# Adafruit_TCS3448_14-Channel_Light_Color_.net
KiCad netlist of a schematic drawn in EAGLE
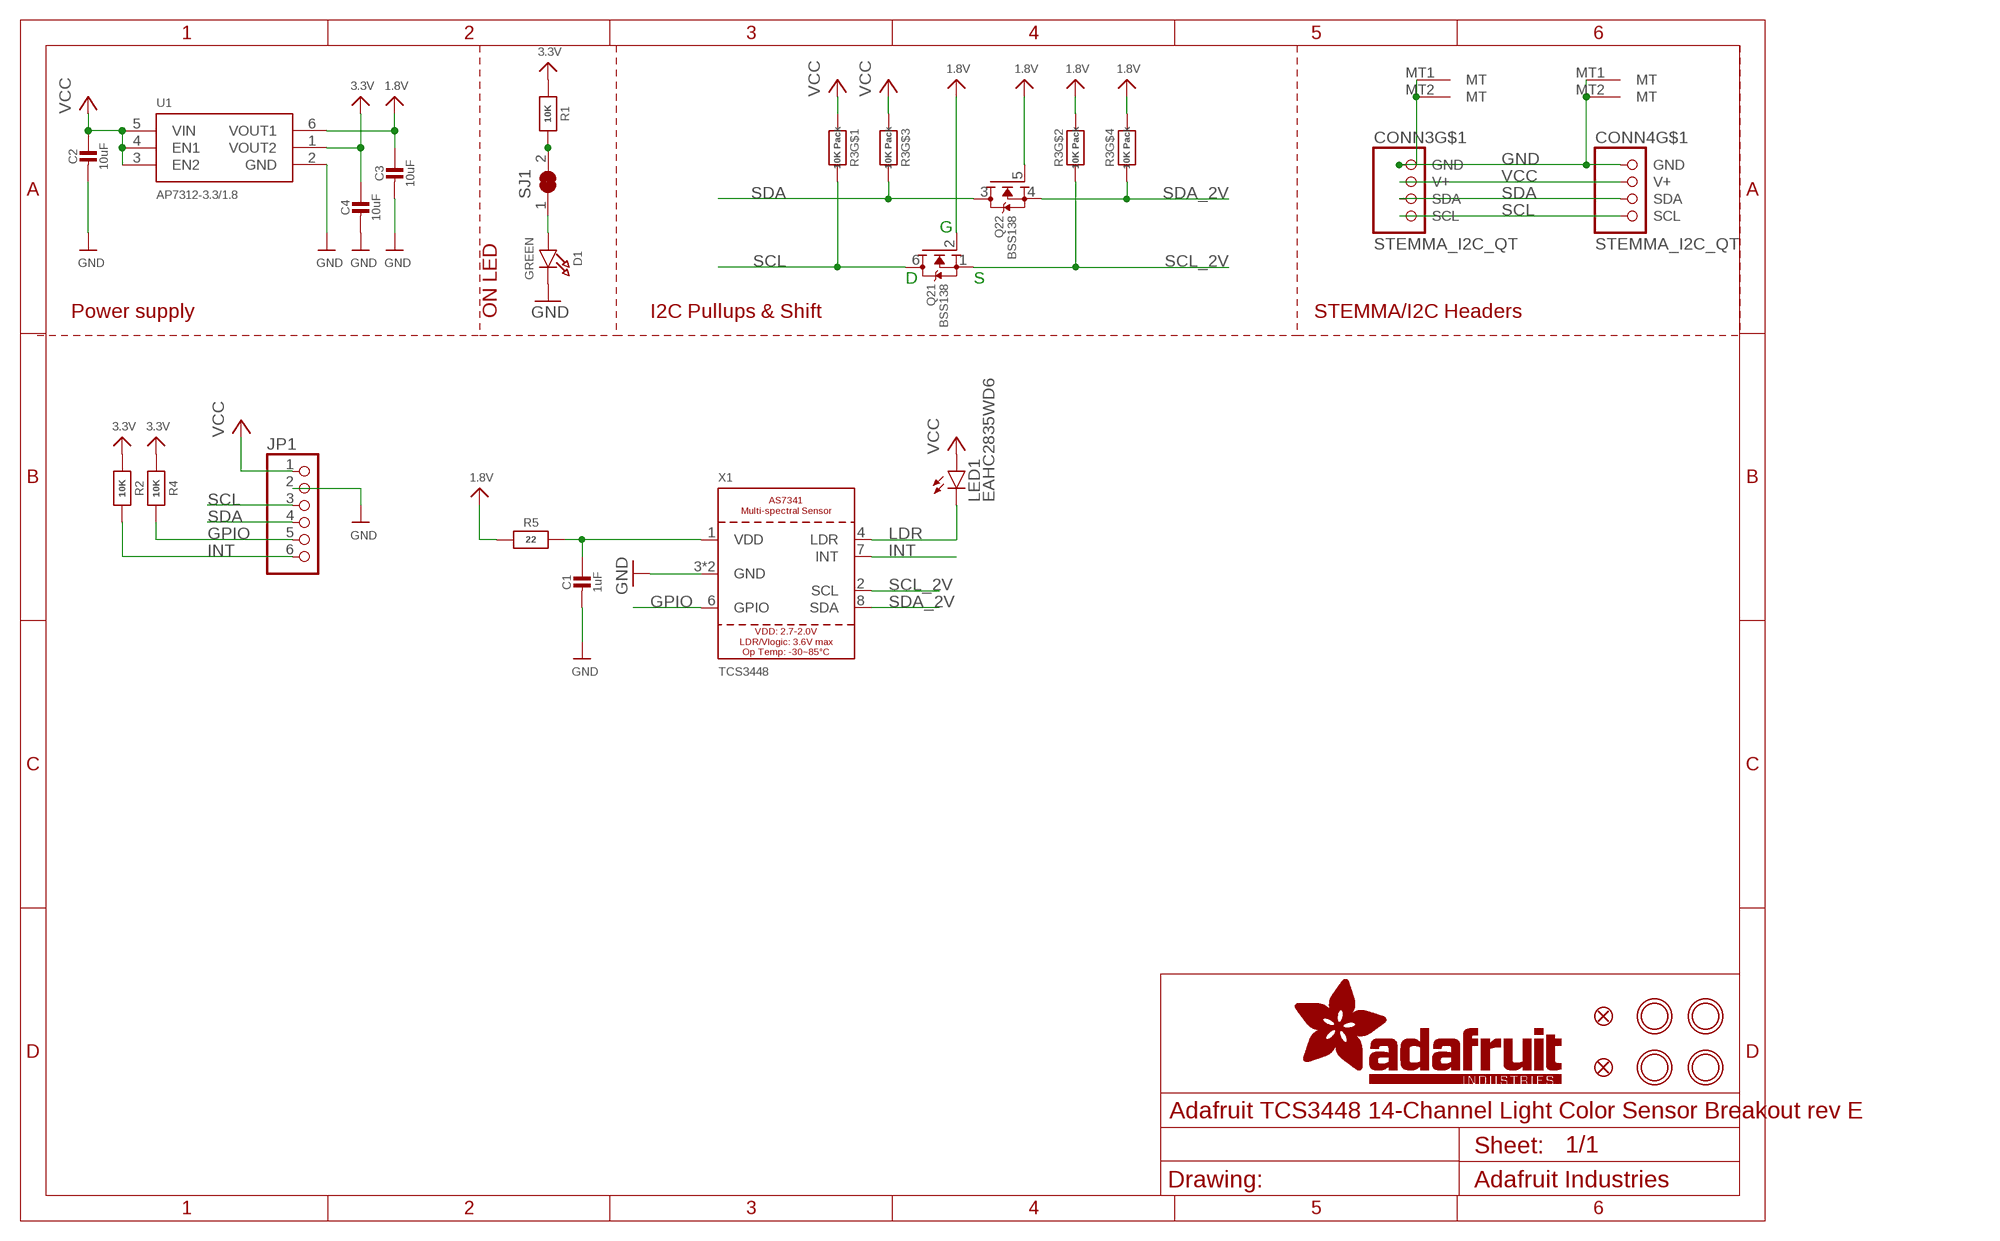
[diagram p0: schematic, sheet 1]

(export (version "E")
  (design (tool "Eeschema 10.0.6"))
  (components
    (comp (ref "C1")
      (value "1uF")
      (footprint "eagle-import:0603-NO")
      (libsource (lib "eagle-import") (part "CAP_CERAMIC0603_NO"))
    )
    (comp (ref "C2")
      (value "10uF")
      (footprint "eagle-import:0805-NO")
      (libsource (lib "eagle-import") (part "CAP_CERAMIC0805-NOOUTLINE"))
    )
    (comp (ref "C3")
      (value "10uF")
      (footprint "eagle-import:0805-NO")
      (libsource (lib "eagle-import") (part "CAP_CERAMIC0805-NOOUTLINE"))
    )
    (comp (ref "C4")
      (value "10uF")
      (footprint "eagle-import:0805-NO")
      (libsource (lib "eagle-import") (part "CAP_CERAMIC0805-NOOUTLINE"))
    )
    (comp (ref "CONN3")
      (value "STEMMA_I2C_QT")
      (footprint "eagle-import:JST_SH4")
      (libsource (lib "eagle-import") (part "STEMMA_I2C_QT"))
    )
    (comp (ref "CONN4")
      (value "STEMMA_I2C_QT")
      (footprint "eagle-import:JST_SH4")
      (libsource (lib "eagle-import") (part "STEMMA_I2C_QT"))
    )
    (comp (ref "D1")
      (value "GREEN")
      (footprint "eagle-import:CHIPLED_0603_NOOUTLINE")
      (libsource (lib "eagle-import") (part "LED0603_NOOUTLINE"))
    )
    (comp (ref "FID3")
      (value "FIDUCIAL_0.5MM")
      (footprint "eagle-import:FIDUCIAL_0.5MM")
      (libsource (lib "eagle-import") (part "FIDUCIAL_0.5MM"))
    )
    (comp (ref "FID4")
      (value "FIDUCIAL_0.5MM")
      (footprint "eagle-import:FIDUCIAL_0.5MM")
      (libsource (lib "eagle-import") (part "FIDUCIAL_0.5MM"))
    )
    (comp (ref "JP1")
      (value "HEADER-1X670MIL")
      (footprint "eagle-import:1X06_ROUND_70")
      (libsource (lib "eagle-import") (part "HEADER-1X670MIL"))
    )
    (comp (ref "LED1")
      (value "EAHC2835WD6")
      (footprint "eagle-import:KA-3528ASYC")
      (libsource (lib "eagle-import") (part "LEDKA-3528ASYC"))
    )
    (comp (ref "Q2")
      (value "BSS138")
      (footprint "eagle-import:SOT363")
      (libsource (lib "eagle-import") (part "MOSFET-N_DUAL"))
    )
    (comp (ref "R1")
      (value "10K")
      (footprint "eagle-import:0603-NO")
      (libsource (lib "eagle-import") (part "RESISTOR_0603_NOOUT"))
    )
    (comp (ref "R2")
      (value "10K")
      (footprint "eagle-import:0603-NO")
      (libsource (lib "eagle-import") (part "RESISTOR_0603_NOOUT"))
    )
    (comp (ref "R3")
      (value "10K Pack")
      (footprint "eagle-import:RESPACK_4X0603")
      (libsource (lib "eagle-import") (part "RESISTOR_4PACK"))
    )
    (comp (ref "R4")
      (value "10K")
      (footprint "eagle-import:0603-NO")
      (libsource (lib "eagle-import") (part "RESISTOR_0603_NOOUT"))
    )
    (comp (ref "R5")
      (value "22")
      (footprint "eagle-import:0603-NO")
      (libsource (lib "eagle-import") (part "RESISTOR_0603_NOOUT"))
    )
    (comp (ref "SJ1")
      (value "SOLDERJUMPER_CLOSED")
      (footprint "eagle-import:SOLDERJUMPER_CLOSEDWIRE")
      (libsource (lib "eagle-import") (part "SOLDERJUMPER_CLOSED"))
    )
    (comp (ref "U$1")
      (value "MOUNTINGHOLE2.5")
      (footprint "eagle-import:MOUNTINGHOLE_2.5_PLATED")
      (libsource (lib "eagle-import") (part "MOUNTINGHOLE2.5"))
    )
    (comp (ref "U$17")
      (value "MOUNTINGHOLE2.5")
      (footprint "eagle-import:MOUNTINGHOLE_2.5_PLATED")
      (libsource (lib "eagle-import") (part "MOUNTINGHOLE2.5"))
    )
    (comp (ref "U$19")
      (value "MOUNTINGHOLE2.5")
      (footprint "eagle-import:MOUNTINGHOLE_2.5_PLATED")
      (libsource (lib "eagle-import") (part "MOUNTINGHOLE2.5"))
    )
    (comp (ref "U$21")
      (value "MOUNTINGHOLE2.5")
      (footprint "eagle-import:MOUNTINGHOLE_2.5_PLATED")
      (libsource (lib "eagle-import") (part "MOUNTINGHOLE2.5"))
    )
    (comp (ref "U1")
      (value "AP7312-3.3/1.8")
      (footprint "eagle-import:SOT23-6")
      (libsource (lib "eagle-import") (part "VREG_SOT23-6_DUALAP7312"))
    )
    (comp (ref "X1")
      (value "TCS3448")
      (footprint "eagle-import:AS7341")
      (libsource (lib "eagle-import") (part "AS7341"))
    )
  )
  (nets
    (net (code "1") (name "/GPIO") (class "Default")
      (node (ref "JP1") (pin "5") (pinfunction "5_5") (pintype "passive"))
      (node (ref "R4") (pin "2") (pinfunction "2_2") (pintype "passive"))
      (node (ref "X1") (pin "6") (pinfunction "GPIO_6") (pintype "power_in"))
    )
    (net (code "2") (name "/INT") (class "Default")
      (node (ref "JP1") (pin "6") (pinfunction "6_6") (pintype "passive"))
      (node (ref "R2") (pin "2") (pinfunction "2_2") (pintype "passive"))
      (node (ref "X1") (pin "7") (pinfunction "INT_7") (pintype "output"))
    )
    (net (code "3") (name "/LDR") (class "Default")
      (node (ref "LED1") (pin "C") (pinfunction "C_C") (pintype "passive"))
      (node (ref "X1") (pin "4") (pinfunction "LDR_4") (pintype "bidirectional"))
    )
    (net (code "4") (name "/SCL") (class "Default")
      (node (ref "CONN3") (pin "4") (pinfunction "SCL_4") (pintype "passive"))
      (node (ref "CONN4") (pin "4") (pinfunction "SCL_4") (pintype "passive"))
      (node (ref "JP1") (pin "3") (pinfunction "3_3") (pintype "passive"))
      (node (ref "Q2") (pin "6") (pinfunction "D_6") (pintype "bidirectional"))
      (node (ref "R3") (pin "8") (pinfunction "2_8") (pintype "passive"))
    )
    (net (code "5") (name "/SCL_2V") (class "Default")
      (node (ref "Q2") (pin "1") (pinfunction "S_1") (pintype "bidirectional"))
      (node (ref "R3") (pin "7") (pinfunction "2_7") (pintype "passive"))
      (node (ref "X1") (pin "2") (pinfunction "SCL_2") (pintype "input"))
    )
    (net (code "6") (name "/SDA") (class "Default")
      (node (ref "CONN3") (pin "3") (pinfunction "SDA_3") (pintype "passive"))
      (node (ref "CONN4") (pin "3") (pinfunction "SDA_3") (pintype "passive"))
      (node (ref "JP1") (pin "4") (pinfunction "4_4") (pintype "passive"))
      (node (ref "Q2") (pin "3") (pinfunction "D_3") (pintype "bidirectional"))
      (node (ref "R3") (pin "6") (pinfunction "2_6") (pintype "passive"))
    )
    (net (code "7") (name "/SDA_2V") (class "Default")
      (node (ref "Q2") (pin "4") (pinfunction "S_4") (pintype "bidirectional"))
      (node (ref "R3") (pin "5") (pinfunction "2_5") (pintype "passive"))
      (node (ref "X1") (pin "8") (pinfunction "SDA_8") (pintype "bidirectional"))
    )
    (net (code "8") (name "1.8V") (class "Default")
      (node (ref "C3") (pin "1") (pinfunction "1_1") (pintype "passive"))
      (node (ref "Q2") (pin "2") (pinfunction "G_2") (pintype "bidirectional"))
      (node (ref "Q2") (pin "5") (pinfunction "G_5") (pintype "bidirectional"))
      (node (ref "R3") (pin "2") (pinfunction "1_2") (pintype "passive"))
      (node (ref "R3") (pin "4") (pinfunction "1_4") (pintype "passive"))
      (node (ref "R5") (pin "1") (pinfunction "1_1") (pintype "passive"))
      (node (ref "U1") (pin "6") (pinfunction "VOUT1_6") (pintype "bidirectional"))
    )
    (net (code "9") (name "3.3V") (class "Default")
      (node (ref "C4") (pin "1") (pinfunction "1_1") (pintype "passive"))
      (node (ref "R1") (pin "1") (pinfunction "1_1") (pintype "passive"))
      (node (ref "R2") (pin "1") (pinfunction "1_1") (pintype "passive"))
      (node (ref "R4") (pin "1") (pinfunction "1_1") (pintype "passive"))
      (node (ref "U1") (pin "1") (pinfunction "VOUT2_1") (pintype "bidirectional"))
    )
    (net (code "10") (name "GND") (class "Default")
      (node (ref "C1") (pin "2") (pinfunction "2_2") (pintype "passive"))
      (node (ref "C2") (pin "2") (pinfunction "2_2") (pintype "passive"))
      (node (ref "C3") (pin "2") (pinfunction "2_2") (pintype "passive"))
      (node (ref "C4") (pin "2") (pinfunction "2_2") (pintype "passive"))
      (node (ref "CONN3") (pin "1") (pinfunction "GND_1") (pintype "passive"))
      (node (ref "CONN3") (pin "MT1") (pinfunction "MT_MT1") (pintype "bidirectional"))
      (node (ref "CONN3") (pin "MT2") (pinfunction "MT_MT2") (pintype "bidirectional"))
      (node (ref "CONN4") (pin "1") (pinfunction "GND_1") (pintype "passive"))
      (node (ref "CONN4") (pin "MT1") (pinfunction "MT_MT1") (pintype "bidirectional"))
      (node (ref "CONN4") (pin "MT2") (pinfunction "MT_MT2") (pintype "bidirectional"))
      (node (ref "D1") (pin "C") (pinfunction "C_C") (pintype "passive"))
      (node (ref "JP1") (pin "2") (pinfunction "2_2") (pintype "passive"))
      (node (ref "U1") (pin "2") (pinfunction "GND_2") (pintype "bidirectional"))
      (node (ref "X1") (pin "3") (pinfunction "GND_3") (pintype "power_in"))
      (node (ref "X1") (pin "5") (pinfunction "GND_5") (pintype "power_in"))
    )
    (net (code "11") (name "Net-(D1-PadA)") (class "Default")
      (node (ref "D1") (pin "A") (pinfunction "A_A") (pintype "passive"))
      (node (ref "SJ1") (pin "1") (pinfunction "1_1") (pintype "passive"))
    )
    (net (code "12") (name "Net-(R1-Pad2)") (class "Default")
      (node (ref "R1") (pin "2") (pinfunction "2_2") (pintype "passive"))
      (node (ref "SJ1") (pin "2") (pinfunction "2_2") (pintype "passive"))
    )
    (net (code "13") (name "Net-(X1-VDD)") (class "Default")
      (node (ref "C1") (pin "1") (pinfunction "1_1") (pintype "passive"))
      (node (ref "R5") (pin "2") (pinfunction "2_2") (pintype "passive"))
      (node (ref "X1") (pin "1") (pinfunction "VDD_1") (pintype "power_in"))
    )
    (net (code "14") (name "VCC") (class "Default")
      (node (ref "C2") (pin "1") (pinfunction "1_1") (pintype "passive"))
      (node (ref "CONN3") (pin "2") (pinfunction "V+_2") (pintype "passive"))
      (node (ref "CONN4") (pin "2") (pinfunction "V+_2") (pintype "passive"))
      (node (ref "JP1") (pin "1") (pinfunction "1_1") (pintype "passive"))
      (node (ref "LED1") (pin "A") (pinfunction "A_A") (pintype "passive"))
      (node (ref "R3") (pin "1") (pinfunction "1_1") (pintype "passive"))
      (node (ref "R3") (pin "3") (pinfunction "1_3") (pintype "passive"))
      (node (ref "U1") (pin "3") (pinfunction "EN2_3") (pintype "bidirectional"))
      (node (ref "U1") (pin "4") (pinfunction "EN1_4") (pintype "bidirectional"))
      (node (ref "U1") (pin "5") (pinfunction "VIN_5") (pintype "bidirectional"))
    )
  )
)
